# LaserTester2.net
KiCad netlist of a schematic drawn in EAGLE
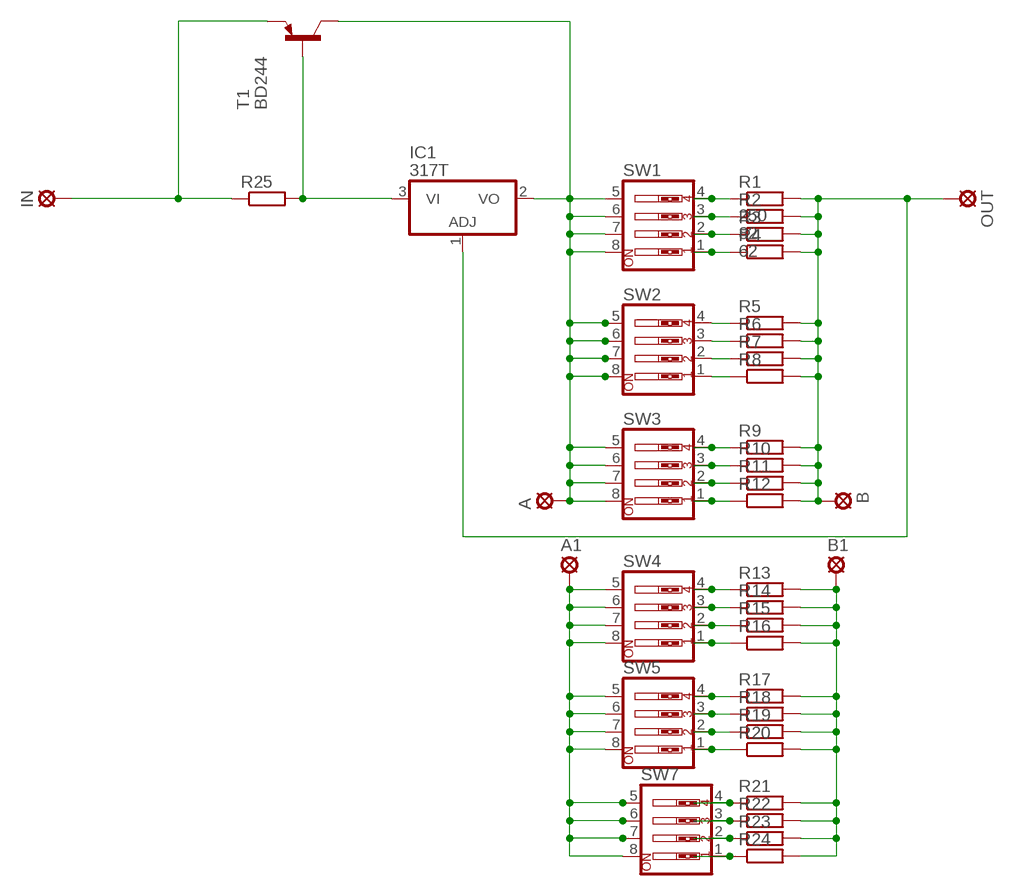
[diagram p0: schematic, sheet 1]

(export (version "E")
  (design (tool "Eeschema 10.0.6"))
  (components
    (comp (ref "A")
      (value "LSP10")
      (footprint "eagle-import:LSP10")
      (libsource (lib "eagle-import") (part "LSP10"))
    )
    (comp (ref "A1")
      (value "LSP10")
      (footprint "eagle-import:LSP10")
      (libsource (lib "eagle-import") (part "LSP10"))
    )
    (comp (ref "B")
      (value "LSP10")
      (footprint "eagle-import:LSP10")
      (libsource (lib "eagle-import") (part "LSP10"))
    )
    (comp (ref "B1")
      (value "LSP10")
      (footprint "eagle-import:LSP10")
      (libsource (lib "eagle-import") (part "LSP10"))
    )
    (comp (ref "IC1")
      (value "317T")
      (footprint "eagle-import:TO220H")
      (libsource (lib "eagle-import") (part "317T"))
    )
    (comp (ref "IN")
      (value "LSP10")
      (footprint "eagle-import:LSP10")
      (libsource (lib "eagle-import") (part "LSP10"))
    )
    (comp (ref "OUT")
      (value "LSP10")
      (footprint "eagle-import:LSP10")
      (libsource (lib "eagle-import") (part "LSP10"))
    )
    (comp (ref "R1")
      (value "250")
      (footprint "eagle-import:0207_10")
      (libsource (lib "eagle-import") (part "resistor_R-EU_0207/10"))
    )
    (comp (ref "R2")
      (value "82")
      (footprint "eagle-import:0207_10")
      (libsource (lib "eagle-import") (part "resistor_R-EU_0207/10"))
    )
    (comp (ref "R3")
      (value "62")
      (footprint "eagle-import:0207_10")
      (libsource (lib "eagle-import") (part "resistor_R-EU_0207/10"))
    )
    (comp (ref "R4")
      (value "R-EU_0207/10")
      (footprint "eagle-import:0207_10")
      (libsource (lib "eagle-import") (part "resistor_R-EU_0207/10"))
    )
    (comp (ref "R5")
      (value "R-EU_0207/10")
      (footprint "eagle-import:0207_10")
      (libsource (lib "eagle-import") (part "resistor_R-EU_0207/10"))
    )
    (comp (ref "R6")
      (value "R-EU_0207/10")
      (footprint "eagle-import:0207_10")
      (libsource (lib "eagle-import") (part "resistor_R-EU_0207/10"))
    )
    (comp (ref "R7")
      (value "R-EU_0207/10")
      (footprint "eagle-import:0207_10")
      (libsource (lib "eagle-import") (part "resistor_R-EU_0207/10"))
    )
    (comp (ref "R8")
      (value "R-EU_0207/10")
      (footprint "eagle-import:0207_10")
      (libsource (lib "eagle-import") (part "resistor_R-EU_0207/10"))
    )
    (comp (ref "R9")
      (value "R-EU_0207/10")
      (footprint "eagle-import:0207_10")
      (libsource (lib "eagle-import") (part "resistor_R-EU_0207/10"))
    )
    (comp (ref "R10")
      (value "R-EU_0207/10")
      (footprint "eagle-import:0207_10")
      (libsource (lib "eagle-import") (part "resistor_R-EU_0207/10"))
    )
    (comp (ref "R11")
      (value "R-EU_0207/10")
      (footprint "eagle-import:0207_10")
      (libsource (lib "eagle-import") (part "resistor_R-EU_0207/10"))
    )
    (comp (ref "R12")
      (value "R-EU_0207/10")
      (footprint "eagle-import:0207_10")
      (libsource (lib "eagle-import") (part "resistor_R-EU_0207/10"))
    )
    (comp (ref "R13")
      (value "R-EU_0207/10")
      (footprint "eagle-import:0207_10")
      (libsource (lib "eagle-import") (part "resistor_R-EU_0207/10"))
    )
    (comp (ref "R14")
      (value "R-EU_0207/10")
      (footprint "eagle-import:0207_10")
      (libsource (lib "eagle-import") (part "resistor_R-EU_0207/10"))
    )
    (comp (ref "R15")
      (value "R-EU_0207/10")
      (footprint "eagle-import:0207_10")
      (libsource (lib "eagle-import") (part "resistor_R-EU_0207/10"))
    )
    (comp (ref "R16")
      (value "R-EU_0207/10")
      (footprint "eagle-import:0207_10")
      (libsource (lib "eagle-import") (part "resistor_R-EU_0207/10"))
    )
    (comp (ref "R17")
      (value "R-EU_0207/10")
      (footprint "eagle-import:0207_10")
      (libsource (lib "eagle-import") (part "resistor_R-EU_0207/10"))
    )
    (comp (ref "R18")
      (value "R-EU_0207/10")
      (footprint "eagle-import:0207_10")
      (libsource (lib "eagle-import") (part "resistor_R-EU_0207/10"))
    )
    (comp (ref "R19")
      (value "R-EU_0207/10")
      (footprint "eagle-import:0207_10")
      (libsource (lib "eagle-import") (part "resistor_R-EU_0207/10"))
    )
    (comp (ref "R20")
      (value "R-EU_0207/10")
      (footprint "eagle-import:0207_10")
      (libsource (lib "eagle-import") (part "resistor_R-EU_0207/10"))
    )
    (comp (ref "R21")
      (value "R-EU_0207/10")
      (footprint "eagle-import:0207_10")
      (libsource (lib "eagle-import") (part "resistor_R-EU_0207/10"))
    )
    (comp (ref "R22")
      (value "R-EU_0207/10")
      (footprint "eagle-import:0207_10")
      (libsource (lib "eagle-import") (part "resistor_R-EU_0207/10"))
    )
    (comp (ref "R23")
      (value "R-EU_0207/10")
      (footprint "eagle-import:0207_10")
      (libsource (lib "eagle-import") (part "resistor_R-EU_0207/10"))
    )
    (comp (ref "R24")
      (value "R-EU_0207/10")
      (footprint "eagle-import:0207_10")
      (libsource (lib "eagle-import") (part "resistor_R-EU_0207/10"))
    )
    (comp (ref "R25")
      (value "R-EU_0207/10")
      (footprint "eagle-import:0207_10")
      (libsource (lib "eagle-import") (part "R-EU_0207/10"))
    )
    (comp (ref "SW1")
      (value "SW_DIP-4")
      (footprint "eagle-import:EDG-04")
      (libsource (lib "eagle-import") (part "SW_DIP-4"))
    )
    (comp (ref "SW2")
      (value "SW_DIP-4")
      (footprint "eagle-import:EDG-04")
      (libsource (lib "eagle-import") (part "SW_DIP-4"))
    )
    (comp (ref "SW3")
      (value "SW_DIP-4")
      (footprint "eagle-import:EDG-04")
      (libsource (lib "eagle-import") (part "SW_DIP-4"))
    )
    (comp (ref "SW4")
      (value "SW_DIP-4")
      (footprint "eagle-import:EDG-04")
      (libsource (lib "eagle-import") (part "SW_DIP-4"))
    )
    (comp (ref "SW5")
      (value "SW_DIP-4")
      (footprint "eagle-import:EDG-04")
      (libsource (lib "eagle-import") (part "SW_DIP-4"))
    )
    (comp (ref "SW7")
      (value "SW_DIP-4")
      (footprint "eagle-import:EDG-04")
      (libsource (lib "eagle-import") (part "SW_DIP-4"))
    )
    (comp (ref "T1")
      (value "BD244")
      (footprint "eagle-import:TO220")
      (libsource (lib "eagle-import") (part "BD244"))
    )
  )
  (nets
    (net (code "1") (name "Net-(A1-PadMP)") (class "Default")
      (node (ref "A1") (pin "MP") (pinfunction "MP_MP") (pintype "passive"))
      (node (ref "SW4") (pin "5") (pinfunction "5_5") (pintype "passive"))
      (node (ref "SW4") (pin "6") (pinfunction "6_6") (pintype "passive"))
      (node (ref "SW4") (pin "7") (pinfunction "7_7") (pintype "passive"))
      (node (ref "SW4") (pin "8") (pinfunction "8_8") (pintype "passive"))
      (node (ref "SW5") (pin "5") (pinfunction "5_5") (pintype "passive"))
      (node (ref "SW5") (pin "6") (pinfunction "6_6") (pintype "passive"))
      (node (ref "SW5") (pin "7") (pinfunction "7_7") (pintype "passive"))
      (node (ref "SW5") (pin "8") (pinfunction "8_8") (pintype "passive"))
      (node (ref "SW7") (pin "5") (pinfunction "5_5") (pintype "passive"))
      (node (ref "SW7") (pin "6") (pinfunction "6_6") (pintype "passive"))
      (node (ref "SW7") (pin "7") (pinfunction "7_7") (pintype "passive"))
      (node (ref "SW7") (pin "8") (pinfunction "8_8") (pintype "passive"))
    )
    (net (code "2") (name "Net-(B1-PadMP)") (class "Default")
      (node (ref "B1") (pin "MP") (pinfunction "MP_MP") (pintype "passive"))
      (node (ref "R13") (pin "2") (pinfunction "2_2") (pintype "passive"))
      (node (ref "R14") (pin "2") (pinfunction "2_2") (pintype "passive"))
      (node (ref "R15") (pin "2") (pinfunction "2_2") (pintype "passive"))
      (node (ref "R16") (pin "2") (pinfunction "2_2") (pintype "passive"))
      (node (ref "R17") (pin "2") (pinfunction "2_2") (pintype "passive"))
      (node (ref "R18") (pin "2") (pinfunction "2_2") (pintype "passive"))
      (node (ref "R19") (pin "2") (pinfunction "2_2") (pintype "passive"))
      (node (ref "R20") (pin "2") (pinfunction "2_2") (pintype "passive"))
      (node (ref "R21") (pin "2") (pinfunction "2_2") (pintype "passive"))
      (node (ref "R22") (pin "2") (pinfunction "2_2") (pintype "passive"))
      (node (ref "R23") (pin "2") (pinfunction "2_2") (pintype "passive"))
      (node (ref "R24") (pin "2") (pinfunction "2_2") (pintype "passive"))
    )
    (net (code "3") (name "Net-(IC1-ADJ)") (class "Default")
      (node (ref "B") (pin "MP") (pinfunction "MP_MP") (pintype "passive"))
      (node (ref "IC1") (pin "1") (pinfunction "ADJ_1") (pintype "input"))
      (node (ref "OUT") (pin "MP") (pinfunction "MP_MP") (pintype "passive"))
      (node (ref "R1") (pin "2") (pinfunction "2_2") (pintype "passive"))
      (node (ref "R10") (pin "2") (pinfunction "2_2") (pintype "passive"))
      (node (ref "R11") (pin "2") (pinfunction "2_2") (pintype "passive"))
      (node (ref "R12") (pin "2") (pinfunction "2_2") (pintype "passive"))
      (node (ref "R2") (pin "2") (pinfunction "2_2") (pintype "passive"))
      (node (ref "R3") (pin "2") (pinfunction "2_2") (pintype "passive"))
      (node (ref "R4") (pin "2") (pinfunction "2_2") (pintype "passive"))
      (node (ref "R5") (pin "2") (pinfunction "2_2") (pintype "passive"))
      (node (ref "R6") (pin "2") (pinfunction "2_2") (pintype "passive"))
      (node (ref "R7") (pin "2") (pinfunction "2_2") (pintype "passive"))
      (node (ref "R8") (pin "2") (pinfunction "2_2") (pintype "passive"))
      (node (ref "R9") (pin "2") (pinfunction "2_2") (pintype "passive"))
    )
    (net (code "4") (name "Net-(IC1-VI)") (class "Default")
      (node (ref "IC1") (pin "3") (pinfunction "VI_3") (pintype "input"))
      (node (ref "R25") (pin "2") (pinfunction "2_2") (pintype "passive"))
      (node (ref "T1") (pin "1") (pinfunction "B_1") (pintype "passive"))
    )
    (net (code "5") (name "Net-(IC1-VO)") (class "Default")
      (node (ref "A") (pin "MP") (pinfunction "MP_MP") (pintype "passive"))
      (node (ref "IC1") (pin "2") (pinfunction "VO_2") (pintype "passive"))
      (node (ref "SW1") (pin "5") (pinfunction "5_5") (pintype "passive"))
      (node (ref "SW1") (pin "6") (pinfunction "6_6") (pintype "passive"))
      (node (ref "SW1") (pin "7") (pinfunction "7_7") (pintype "passive"))
      (node (ref "SW1") (pin "8") (pinfunction "8_8") (pintype "passive"))
      (node (ref "SW2") (pin "5") (pinfunction "5_5") (pintype "passive"))
      (node (ref "SW2") (pin "6") (pinfunction "6_6") (pintype "passive"))
      (node (ref "SW2") (pin "7") (pinfunction "7_7") (pintype "passive"))
      (node (ref "SW2") (pin "8") (pinfunction "8_8") (pintype "passive"))
      (node (ref "SW3") (pin "5") (pinfunction "5_5") (pintype "passive"))
      (node (ref "SW3") (pin "6") (pinfunction "6_6") (pintype "passive"))
      (node (ref "SW3") (pin "7") (pinfunction "7_7") (pintype "passive"))
      (node (ref "SW3") (pin "8") (pinfunction "8_8") (pintype "passive"))
      (node (ref "T1") (pin "2") (pinfunction "C_2") (pintype "passive"))
    )
    (net (code "6") (name "Net-(R1-Pad1)") (class "Default")
      (node (ref "R1") (pin "1") (pinfunction "1_1") (pintype "passive"))
      (node (ref "SW1") (pin "4") (pinfunction "4_4") (pintype "passive"))
    )
    (net (code "7") (name "Net-(R2-Pad1)") (class "Default")
      (node (ref "R2") (pin "1") (pinfunction "1_1") (pintype "passive"))
      (node (ref "SW1") (pin "3") (pinfunction "3_3") (pintype "passive"))
    )
    (net (code "8") (name "Net-(R3-Pad1)") (class "Default")
      (node (ref "R3") (pin "1") (pinfunction "1_1") (pintype "passive"))
      (node (ref "SW1") (pin "2") (pinfunction "2_2") (pintype "passive"))
    )
    (net (code "9") (name "Net-(R4-Pad1)") (class "Default")
      (node (ref "R4") (pin "1") (pinfunction "1_1") (pintype "passive"))
      (node (ref "SW1") (pin "1") (pinfunction "1_1") (pintype "passive"))
    )
    (net (code "10") (name "Net-(R5-Pad1)") (class "Default")
      (node (ref "R5") (pin "1") (pinfunction "1_1") (pintype "passive"))
      (node (ref "SW2") (pin "4") (pinfunction "4_4") (pintype "passive"))
    )
    (net (code "11") (name "Net-(R6-Pad1)") (class "Default")
      (node (ref "R6") (pin "1") (pinfunction "1_1") (pintype "passive"))
      (node (ref "SW2") (pin "3") (pinfunction "3_3") (pintype "passive"))
    )
    (net (code "12") (name "Net-(R7-Pad1)") (class "Default")
      (node (ref "R7") (pin "1") (pinfunction "1_1") (pintype "passive"))
      (node (ref "SW2") (pin "2") (pinfunction "2_2") (pintype "passive"))
    )
    (net (code "13") (name "Net-(R8-Pad1)") (class "Default")
      (node (ref "R8") (pin "1") (pinfunction "1_1") (pintype "passive"))
      (node (ref "SW2") (pin "1") (pinfunction "1_1") (pintype "passive"))
    )
    (net (code "14") (name "Net-(R9-Pad1)") (class "Default")
      (node (ref "R9") (pin "1") (pinfunction "1_1") (pintype "passive"))
      (node (ref "SW3") (pin "4") (pinfunction "4_4") (pintype "passive"))
    )
    (net (code "15") (name "Net-(R10-Pad1)") (class "Default")
      (node (ref "R10") (pin "1") (pinfunction "1_1") (pintype "passive"))
      (node (ref "SW3") (pin "3") (pinfunction "3_3") (pintype "passive"))
    )
    (net (code "16") (name "Net-(R11-Pad1)") (class "Default")
      (node (ref "R11") (pin "1") (pinfunction "1_1") (pintype "passive"))
      (node (ref "SW3") (pin "2") (pinfunction "2_2") (pintype "passive"))
    )
    (net (code "17") (name "Net-(R12-Pad1)") (class "Default")
      (node (ref "R12") (pin "1") (pinfunction "1_1") (pintype "passive"))
      (node (ref "SW3") (pin "1") (pinfunction "1_1") (pintype "passive"))
    )
    (net (code "18") (name "Net-(R13-Pad1)") (class "Default")
      (node (ref "R13") (pin "1") (pinfunction "1_1") (pintype "passive"))
      (node (ref "SW4") (pin "4") (pinfunction "4_4") (pintype "passive"))
    )
    (net (code "19") (name "Net-(R14-Pad1)") (class "Default")
      (node (ref "R14") (pin "1") (pinfunction "1_1") (pintype "passive"))
      (node (ref "SW4") (pin "3") (pinfunction "3_3") (pintype "passive"))
    )
    (net (code "20") (name "Net-(R15-Pad1)") (class "Default")
      (node (ref "R15") (pin "1") (pinfunction "1_1") (pintype "passive"))
      (node (ref "SW4") (pin "2") (pinfunction "2_2") (pintype "passive"))
    )
    (net (code "21") (name "Net-(R16-Pad1)") (class "Default")
      (node (ref "R16") (pin "1") (pinfunction "1_1") (pintype "passive"))
      (node (ref "SW4") (pin "1") (pinfunction "1_1") (pintype "passive"))
    )
    (net (code "22") (name "Net-(R17-Pad1)") (class "Default")
      (node (ref "R17") (pin "1") (pinfunction "1_1") (pintype "passive"))
      (node (ref "SW5") (pin "4") (pinfunction "4_4") (pintype "passive"))
    )
    (net (code "23") (name "Net-(R18-Pad1)") (class "Default")
      (node (ref "R18") (pin "1") (pinfunction "1_1") (pintype "passive"))
      (node (ref "SW5") (pin "3") (pinfunction "3_3") (pintype "passive"))
    )
    (net (code "24") (name "Net-(R19-Pad1)") (class "Default")
      (node (ref "R19") (pin "1") (pinfunction "1_1") (pintype "passive"))
      (node (ref "SW5") (pin "2") (pinfunction "2_2") (pintype "passive"))
    )
    (net (code "25") (name "Net-(R20-Pad1)") (class "Default")
      (node (ref "R20") (pin "1") (pinfunction "1_1") (pintype "passive"))
      (node (ref "SW5") (pin "1") (pinfunction "1_1") (pintype "passive"))
    )
    (net (code "26") (name "Net-(R21-Pad1)") (class "Default")
      (node (ref "R21") (pin "1") (pinfunction "1_1") (pintype "passive"))
      (node (ref "SW7") (pin "4") (pinfunction "4_4") (pintype "passive"))
    )
    (net (code "27") (name "Net-(R22-Pad1)") (class "Default")
      (node (ref "R22") (pin "1") (pinfunction "1_1") (pintype "passive"))
      (node (ref "SW7") (pin "3") (pinfunction "3_3") (pintype "passive"))
    )
    (net (code "28") (name "Net-(R23-Pad1)") (class "Default")
      (node (ref "R23") (pin "1") (pinfunction "1_1") (pintype "passive"))
      (node (ref "SW7") (pin "2") (pinfunction "2_2") (pintype "passive"))
    )
    (net (code "29") (name "Net-(R24-Pad1)") (class "Default")
      (node (ref "R24") (pin "1") (pinfunction "1_1") (pintype "passive"))
      (node (ref "SW7") (pin "1") (pinfunction "1_1") (pintype "passive"))
    )
    (net (code "30") (name "Net-(T1-E)") (class "Default")
      (node (ref "IN") (pin "MP") (pinfunction "MP_MP") (pintype "passive"))
      (node (ref "R25") (pin "1") (pinfunction "1_1") (pintype "passive"))
      (node (ref "T1") (pin "3") (pinfunction "E_3") (pintype "passive"))
    )
  )
)
